# ultrasonic_rx.net
KiCad netlist of a schematic drawn in Altium Designer
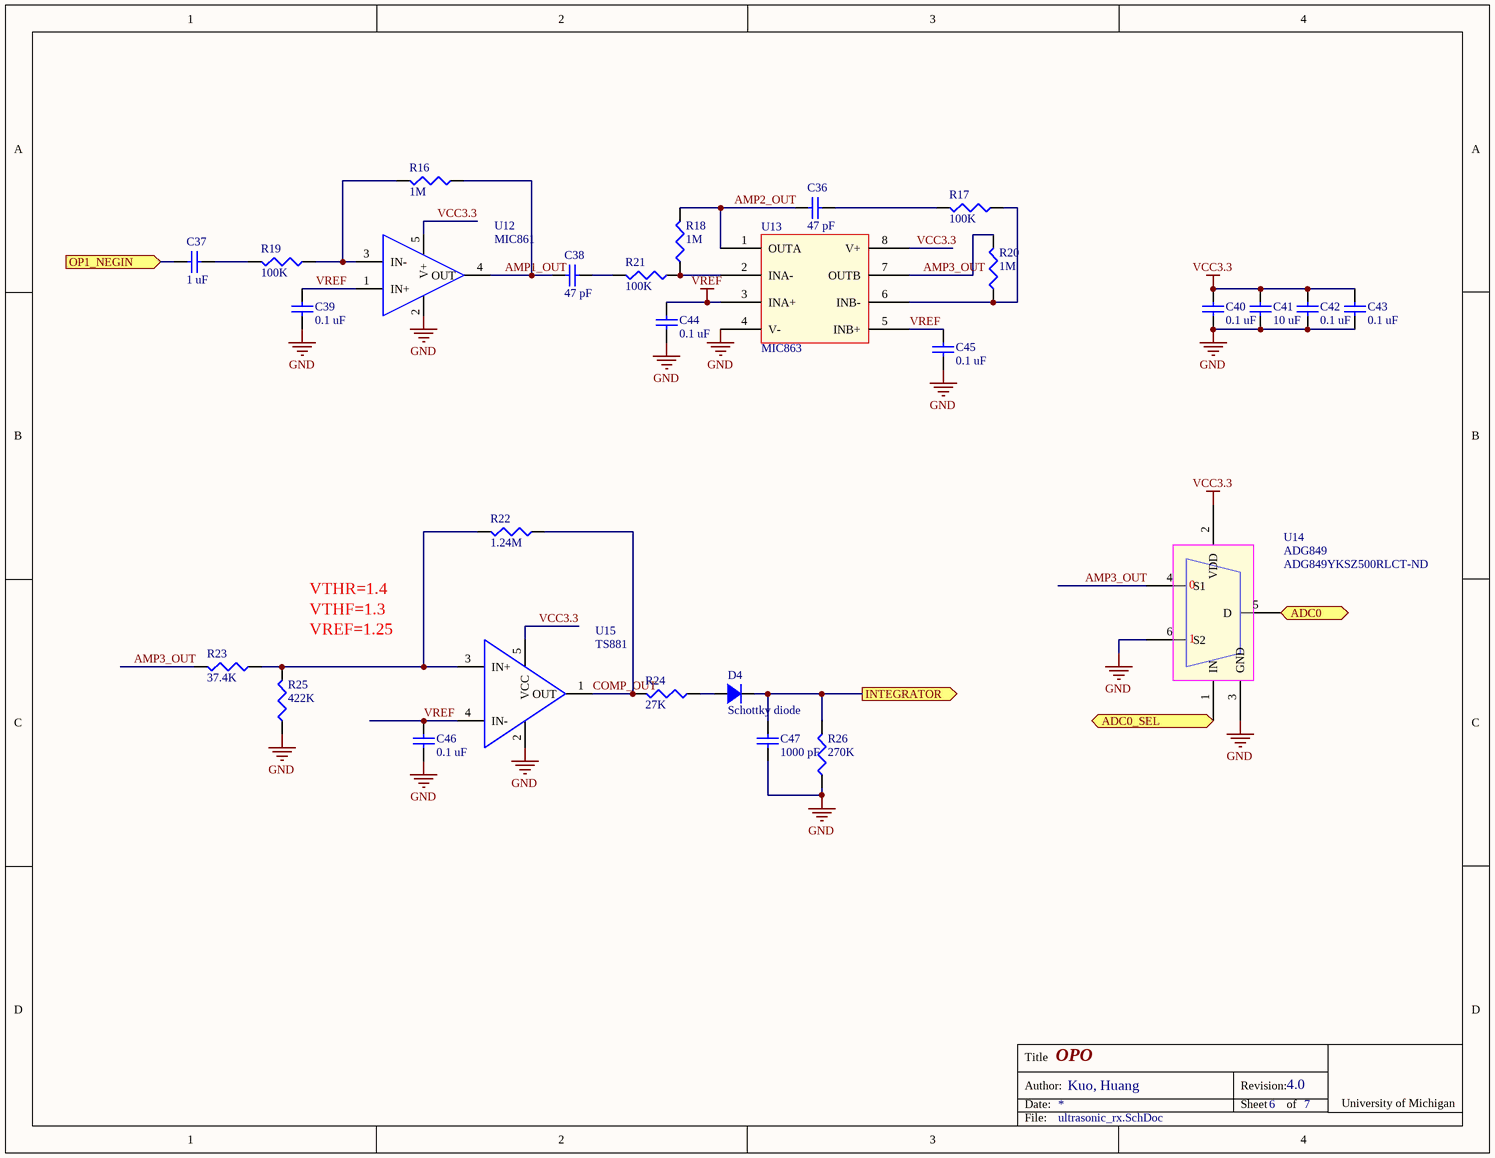
[diagram p0: ultrasonic_rx.SchDoc]

(export (version "E")
  (design (tool "Eeschema 10.0.6"))
  (components
    (comp (ref "C36")
      (value "47 pF")
      (footprint "0402")
      (description "Ceramic capacitor, 47 pF, 0402 package")
      (fields (field (name "TOLERANCE") "5%") (field (name "Comment") "Ceramic capacitor"))
      (libsource (lib "rlc") (part "C_47p_0402_ceramic"))
    )
    (comp (ref "C37")
      (value "1 uF")
      (footprint "0402")
      (description "Ceramic capacitor, 1 uF, 0402 package")
      (fields (field (name "TOLERANCE") "10%") (field (name "Comment") "Ceramic capacitor"))
      (libsource (lib "rlc") (part "C_1u_0402_ceramic"))
    )
    (comp (ref "C38")
      (value "47 pF")
      (footprint "0402")
      (description "Ceramic capacitor, 47 pF, 0402 package")
      (fields (field (name "TOLERANCE") "5%") (field (name "Comment") "Ceramic capacitor"))
      (libsource (lib "rlc") (part "C_47p_0402_ceramic"))
    )
    (comp (ref "C39")
      (value "0.1 uF")
      (footprint "0402")
      (description "Ceramic capacitor, 0.1u, 0402 package")
      (fields (field (name "TOLERANCE") "10%") (field (name "Comment") "Ceramic capacitor"))
      (libsource (lib "rlc") (part "C_0.1u_0402_ceramic"))
    )
    (comp (ref "C40")
      (value "0.1 uF")
      (footprint "0402")
      (description "Ceramic capacitor, 0.1u, 0402 package")
      (fields (field (name "TOLERANCE") "10%") (field (name "Comment") "Ceramic capacitor"))
      (libsource (lib "rlc") (part "C_0.1u_0402_ceramic"))
    )
    (comp (ref "C41")
      (value "10 uF")
      (footprint "0603")
      (description "Ceramic capacitor, 10 uF, 0603 package")
      (fields (field (name "TOLERANCE") "20%") (field (name "Comment") "Ceramic capacitor"))
      (libsource (lib "rlc") (part "C_10u_0603_ceramic"))
    )
    (comp (ref "C42")
      (value "0.1 uF")
      (footprint "0402")
      (description "Ceramic capacitor, 0.1u, 0402 package")
      (fields (field (name "TOLERANCE") "10%") (field (name "Comment") "Ceramic capacitor"))
      (libsource (lib "rlc") (part "C_0.1u_0402_ceramic"))
    )
    (comp (ref "C43")
      (value "0.1 uF")
      (footprint "0402")
      (description "Ceramic capacitor, 0.1u, 0402 package")
      (fields (field (name "TOLERANCE") "10%") (field (name "Comment") "Ceramic capacitor"))
      (libsource (lib "rlc") (part "C_0.1u_0402_ceramic"))
    )
    (comp (ref "C44")
      (value "0.1 uF")
      (footprint "0402")
      (description "Ceramic capacitor, 0.1u, 0402 package")
      (fields (field (name "TOLERANCE") "10%") (field (name "Comment") "Ceramic capacitor"))
      (libsource (lib "rlc") (part "C_0.1u_0402_ceramic"))
    )
    (comp (ref "C45")
      (value "0.1 uF")
      (footprint "0402")
      (description "Ceramic capacitor, 0.1u, 0402 package")
      (fields (field (name "TOLERANCE") "10%") (field (name "Comment") "Ceramic capacitor"))
      (libsource (lib "rlc") (part "C_0.1u_0402_ceramic"))
    )
    (comp (ref "C46")
      (value "0.1 uF")
      (footprint "0402")
      (description "Ceramic capacitor, 0.1u, 0402 package")
      (fields (field (name "TOLERANCE") "10%") (field (name "Comment") "Ceramic capacitor"))
      (libsource (lib "rlc") (part "C_0.1u_0402_ceramic"))
    )
    (comp (ref "C47")
      (value "1000 pF")
      (footprint "0402")
      (description "Ceramic capacitor, 1000 pF, 0402 package")
      (fields (field (name "TOLERANCE") "10%") (field (name "Comment") "Ceramic capacitor"))
      (libsource (lib "rlc") (part "C_1000p_0402_ceramic"))
    )
    (comp (ref "D4")
      (value "Schottky diode")
      (footprint "0603 - DIODE")
      (description "Schottky diode 30 V 0.1 A 0603")
      (libsource (lib "rlc") (part "D_SCHOTTKY_30V_0.1A_0603"))
    )
    (comp (ref "R16")
      (value "1M")
      (footprint "0402")
      (description "Chip resistor, 1M, 0402 package")
      (fields (field (name "TOLERANCE") "1%") (field (name "POWER") "1/16 W"))
      (libsource (lib "rlc") (part "R_1M_0402"))
    )
    (comp (ref "R17")
      (value "100K")
      (footprint "0402")
      (description "Chip resistor, 100K, 0402 package")
      (fields (field (name "TOLERANCE") "1%") (field (name "POWER") "1/16 W"))
      (libsource (lib "rlc") (part "R_100K_0402"))
    )
    (comp (ref "R18")
      (value "1M")
      (footprint "0402")
      (description "Chip resistor, 1M, 0402 package")
      (fields (field (name "TOLERANCE") "1%") (field (name "POWER") "1/16 W"))
      (libsource (lib "rlc") (part "R_1M_0402"))
    )
    (comp (ref "R19")
      (value "100K")
      (footprint "0402")
      (description "Chip resistor, 100K, 0402 package")
      (fields (field (name "TOLERANCE") "1%") (field (name "POWER") "1/16 W"))
      (libsource (lib "rlc") (part "R_100K_0402"))
    )
    (comp (ref "R20")
      (value "1M")
      (footprint "0402")
      (description "Chip resistor, 1M, 0402 package")
      (fields (field (name "TOLERANCE") "1%") (field (name "POWER") "1/16 W"))
      (libsource (lib "rlc") (part "R_1M_0402"))
    )
    (comp (ref "R21")
      (value "100K")
      (footprint "0402")
      (description "Chip resistor, 100K, 0402 package")
      (fields (field (name "TOLERANCE") "1%") (field (name "POWER") "1/16 W"))
      (libsource (lib "rlc") (part "R_100K_0402"))
    )
    (comp (ref "R22")
      (value "1.24M")
      (footprint "0402")
      (description "Chip resistor, 1.24M, 0402 package")
      (fields (field (name "TOLERANCE") "1%") (field (name "POWER") "1/16 W"))
      (libsource (lib "rlc") (part "R_1.24M_0402"))
    )
    (comp (ref "R23")
      (value "37.4K")
      (footprint "0402")
      (description "Chip resistor, 37.4K, 0402 package")
      (fields (field (name "TOLERANCE") "1%") (field (name "POWER") "1/16 W"))
      (libsource (lib "rlc") (part "R_37.4K_0402"))
    )
    (comp (ref "R24")
      (value "27K")
      (footprint "0402")
      (description "Chip resistor, 27K, 0402 package")
      (fields (field (name "TOLERANCE") "1%") (field (name "POWER") "1/16 W"))
      (libsource (lib "rlc") (part "R_27K_0402"))
    )
    (comp (ref "R25")
      (value "422K")
      (footprint "0402")
      (description "Chip resistor, 422K, 0402 package")
      (fields (field (name "TOLERANCE") "1%") (field (name "POWER") "1/16 W"))
      (libsource (lib "rlc") (part "R_422K_0402"))
    )
    (comp (ref "R26")
      (value "270K")
      (footprint "0402")
      (description "Chip resistor, 270K, 0402 package")
      (fields (field (name "TOLERANCE") "1%") (field (name "POWER") "1/16 W"))
      (libsource (lib "rlc") (part "R_270K_0402"))
    )
    (comp (ref "U12")
      (value "MIC861")
      (footprint "SC70-5")
      (description "IC OPAMP 400KHZ 2.7V ULT LP SC70")
      (libsource (lib "opo") (part "MIC861"))
    )
    (comp (ref "U13")
      (value "MIC863")
      (footprint "TSOP65P280X145-8N")
      (description "Dual Ultra Low Power Op Amp in SOT23-8")
      (libsource (lib "opo") (part "MIC863"))
    )
    (comp (ref "U14")
      (value "ADG849")
      (footprint "SC70-6")
      (description "0.5 Ω SPDT/2:1 Mux in SC70")
      (fields (field (name "SUPPLIER PART NUMBER 1") "ADG849YKSZ500RLCT-ND"))
      (libsource (lib "opo") (part "ADG849"))
    )
    (comp (ref "U15")
      (value "TS881")
      (footprint "SC70-5")
      (description "Rail-to-rail 1.1 V nanopower comparator")
      (libsource (lib "opo") (part "TS881"))
    )
  )
  (nets
    (net (code "1") (name "/ADC0") (class "Default")
      (node (ref "U14") (pin "5") (pinfunction "D_5") (pintype "passive"))
    )
    (net (code "2") (name "/ADC0_SEL") (class "Default")
      (node (ref "U14") (pin "1") (pinfunction "IN_1") (pintype "passive"))
    )
    (net (code "3") (name "/AMP1_OUT") (class "Default")
      (node (ref "C38") (pin "1") (pintype "passive"))
      (node (ref "R16") (pin "2") (pintype "passive"))
      (node (ref "U12") (pin "4") (pinfunction "OUT_4") (pintype "passive"))
    )
    (net (code "4") (name "/AMP2_OUT") (class "Default")
      (node (ref "C36") (pin "1") (pintype "passive"))
      (node (ref "R18") (pin "1") (pintype "passive"))
      (node (ref "U13") (pin "1") (pinfunction "OUTA_1") (pintype "passive"))
    )
    (net (code "5") (name "/AMP3_OUT") (class "Default")
      (node (ref "R20") (pin "1") (pintype "passive"))
      (node (ref "R23") (pin "1") (pintype "passive"))
      (node (ref "U13") (pin "7") (pinfunction "OUTB_7") (pintype "passive"))
      (node (ref "U14") (pin "4") (pinfunction "S1_4") (pintype "passive"))
    )
    (net (code "6") (name "/COMP_OUT") (class "Default")
      (node (ref "R22") (pin "2") (pintype "passive"))
      (node (ref "R24") (pin "1") (pintype "passive"))
      (node (ref "U15") (pin "1") (pinfunction "OUT_1") (pintype "passive"))
    )
    (net (code "7") (name "/INTEGRATOR") (class "Default")
      (node (ref "C47") (pin "1") (pintype "passive"))
      (node (ref "D4") (pin "2") (pintype "passive"))
      (node (ref "R26") (pin "1") (pintype "passive"))
    )
    (net (code "8") (name "/OP1_NEGIN") (class "Default") (node (ref "C37") (pin "1") (pintype "passive")))
    (net (code "9") (name "GND") (class "Default")
      (node (ref "C39") (pin "2") (pintype "passive"))
      (node (ref "C40") (pin "2") (pintype "passive"))
      (node (ref "C41") (pin "2") (pintype "passive"))
      (node (ref "C42") (pin "2") (pintype "passive"))
      (node (ref "C43") (pin "2") (pintype "passive"))
      (node (ref "C44") (pin "2") (pintype "passive"))
      (node (ref "C45") (pin "2") (pintype "passive"))
      (node (ref "C46") (pin "2") (pintype "passive"))
      (node (ref "C47") (pin "2") (pintype "passive"))
      (node (ref "R25") (pin "2") (pintype "passive"))
      (node (ref "R26") (pin "2") (pintype "passive"))
      (node (ref "U12") (pin "2") (pinfunction "V-_2") (pintype "passive"))
      (node (ref "U13") (pin "4") (pinfunction "V-_4") (pintype "passive"))
      (node (ref "U14") (pin "3") (pinfunction "GND_3") (pintype "passive"))
      (node (ref "U14") (pin "6") (pinfunction "S2_6") (pintype "passive"))
      (node (ref "U15") (pin "2") (pinfunction "VEE_2") (pintype "passive"))
    )
    (net (code "10") (name "Net-(C36-Pad2)") (class "Default")
      (node (ref "C36") (pin "2") (pintype "passive"))
      (node (ref "R17") (pin "1") (pintype "passive"))
    )
    (net (code "11") (name "Net-(C37-Pad2)") (class "Default")
      (node (ref "C37") (pin "2") (pintype "passive"))
      (node (ref "R19") (pin "1") (pintype "passive"))
    )
    (net (code "12") (name "Net-(C38-Pad2)") (class "Default")
      (node (ref "C38") (pin "2") (pintype "passive"))
      (node (ref "R21") (pin "1") (pintype "passive"))
    )
    (net (code "13") (name "Net-(D4-Pad1)") (class "Default")
      (node (ref "D4") (pin "1") (pintype "passive"))
      (node (ref "R24") (pin "2") (pintype "passive"))
    )
    (net (code "14") (name "Net-(U12-IN-)") (class "Default")
      (node (ref "R16") (pin "1") (pintype "passive"))
      (node (ref "R19") (pin "2") (pintype "passive"))
      (node (ref "U12") (pin "3") (pinfunction "IN-_3") (pintype "passive"))
    )
    (net (code "15") (name "Net-(U13-INA-)") (class "Default")
      (node (ref "R18") (pin "2") (pintype "passive"))
      (node (ref "R21") (pin "2") (pintype "passive"))
      (node (ref "U13") (pin "2") (pinfunction "INA-_2") (pintype "passive"))
    )
    (net (code "16") (name "Net-(U13-INB-)") (class "Default")
      (node (ref "R17") (pin "2") (pintype "passive"))
      (node (ref "R20") (pin "2") (pintype "passive"))
      (node (ref "U13") (pin "6") (pinfunction "INB-_6") (pintype "passive"))
    )
    (net (code "17") (name "Net-(U15-IN+)") (class "Default")
      (node (ref "R22") (pin "1") (pintype "passive"))
      (node (ref "R23") (pin "2") (pintype "passive"))
      (node (ref "R25") (pin "1") (pintype "passive"))
      (node (ref "U15") (pin "3") (pinfunction "IN+_3") (pintype "passive"))
    )
    (net (code "18") (name "VCC3.3") (class "Default")
      (node (ref "C40") (pin "1") (pintype "passive"))
      (node (ref "C41") (pin "1") (pintype "passive"))
      (node (ref "C42") (pin "1") (pintype "passive"))
      (node (ref "C43") (pin "1") (pintype "passive"))
      (node (ref "U12") (pin "5") (pinfunction "V+_5") (pintype "passive"))
      (node (ref "U13") (pin "8") (pinfunction "V+_8") (pintype "passive"))
      (node (ref "U14") (pin "2") (pinfunction "VDD_2") (pintype "passive"))
      (node (ref "U15") (pin "5") (pinfunction "VCC_5") (pintype "passive"))
    )
    (net (code "19") (name "VREF") (class "Default")
      (node (ref "C39") (pin "1") (pintype "passive"))
      (node (ref "C44") (pin "1") (pintype "passive"))
      (node (ref "C45") (pin "1") (pintype "passive"))
      (node (ref "C46") (pin "1") (pintype "passive"))
      (node (ref "U12") (pin "1") (pinfunction "IN+_1") (pintype "passive"))
      (node (ref "U13") (pin "3") (pinfunction "INA+_3") (pintype "passive"))
      (node (ref "U13") (pin "5") (pinfunction "INB+_5") (pintype "passive"))
      (node (ref "U15") (pin "4") (pinfunction "IN-_4") (pintype "passive"))
    )
  )
)
